# MiniMoto.net
KiCad netlist of a schematic drawn in EAGLE
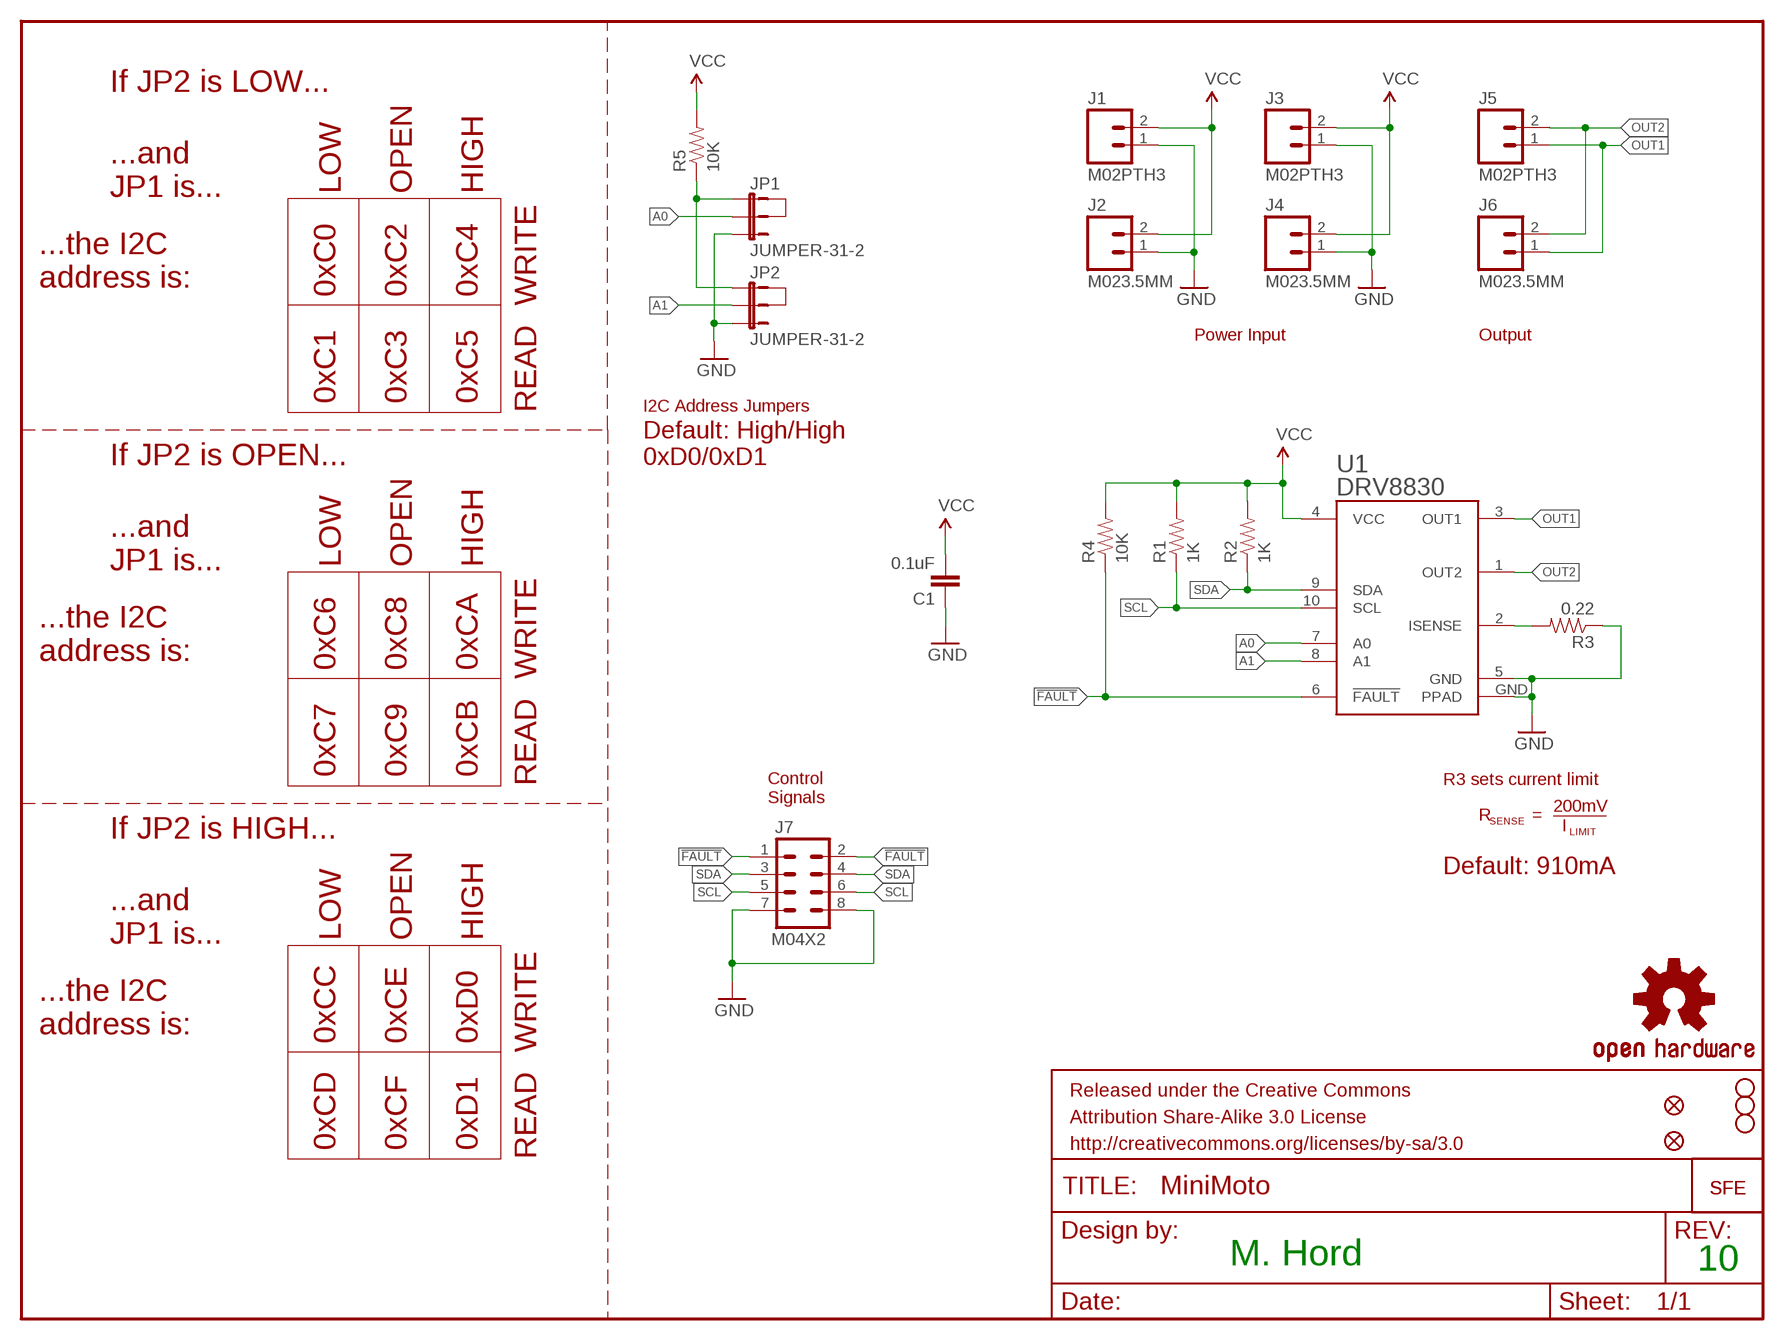
[diagram p0: schematic, sheet 1]

(export (version "E")
  (design (tool "Eeschema 10.0.6"))
  (components
    (comp (ref "C1")
      (value "0.1uF")
      (footprint "eagle-import:0603-CAP")
      (libsource (lib "eagle-import") (part "0.1UF-25V(+80/-20%)(0603)"))
    )
    (comp (ref "FID1")
      (value "FIDUCIALUFIDUCIAL")
      (footprint "eagle-import:MICRO-FIDUCIAL")
      (libsource (lib "eagle-import") (part "FIDUCIALUFIDUCIAL"))
    )
    (comp (ref "FID2")
      (value "FIDUCIALUFIDUCIAL")
      (footprint "eagle-import:MICRO-FIDUCIAL")
      (libsource (lib "eagle-import") (part "FIDUCIALUFIDUCIAL"))
    )
    (comp (ref "FRAME1")
      (value "FRAME-LETTER")
      (footprint "eagle-import:CREATIVE_COMMONS")
      (libsource (lib "eagle-import") (part "FRAME-LETTER"))
    )
    (comp (ref "J1")
      (value "M02PTH3")
      (footprint "eagle-import:1X02_LONGPADS")
      (libsource (lib "eagle-import") (part "M02PTH3"))
    )
    (comp (ref "J2")
      (value "M023.5MM")
      (footprint "eagle-import:SCREWTERMINAL-3.5MM-2")
      (libsource (lib "eagle-import") (part "M023.5MM"))
    )
    (comp (ref "J3")
      (value "M02PTH3")
      (footprint "eagle-import:1X02_LONGPADS")
      (libsource (lib "eagle-import") (part "M02PTH3"))
    )
    (comp (ref "J4")
      (value "M023.5MM")
      (footprint "eagle-import:SCREWTERMINAL-3.5MM-2")
      (libsource (lib "eagle-import") (part "M023.5MM"))
    )
    (comp (ref "J5")
      (value "M02PTH3")
      (footprint "eagle-import:1X02_LONGPADS")
      (libsource (lib "eagle-import") (part "M02PTH3"))
    )
    (comp (ref "J6")
      (value "M023.5MM")
      (footprint "eagle-import:SCREWTERMINAL-3.5MM-2")
      (libsource (lib "eagle-import") (part "M023.5MM"))
    )
    (comp (ref "J7")
      (value "M04X2")
      (footprint "eagle-import:2X4")
      (libsource (lib "eagle-import") (part "M04X2"))
    )
    (comp (ref "JP1")
      (value "JUMPER-31-2")
      (footprint "eagle-import:SJ_3_PASTE1&2")
      (libsource (lib "eagle-import") (part "JUMPER-31-2"))
    )
    (comp (ref "JP2")
      (value "JUMPER-31-2")
      (footprint "eagle-import:SJ_3_PASTE1&2")
      (libsource (lib "eagle-import") (part "JUMPER-31-2"))
    )
    (comp (ref "LOGO1")
      (value "LOGO-SFESK")
      (footprint "eagle-import:SFE-LOGO-FLAME")
      (libsource (lib "eagle-import") (part "LOGO-SFESK"))
    )
    (comp (ref "LOGO2")
      (value "OSHW-LOGOS")
      (footprint "eagle-import:OSHW-LOGO-S")
      (libsource (lib "eagle-import") (part "OSHW-LOGOS"))
    )
    (comp (ref "LOGO3")
      (value "LOGO-SFESK")
      (footprint "eagle-import:SFE-LOGO-FLAME")
      (libsource (lib "eagle-import") (part "LOGO-SFESK"))
    )
    (comp (ref "R1")
      (value "1K")
      (footprint "eagle-import:0603-RES")
      (libsource (lib "eagle-import") (part "1KOHM1/10W1%(0603)"))
    )
    (comp (ref "R2")
      (value "1K")
      (footprint "eagle-import:0603-RES")
      (libsource (lib "eagle-import") (part "1KOHM1/10W1%(0603)"))
    )
    (comp (ref "R3")
      (value "0.22")
      (footprint "eagle-import:0805")
      (libsource (lib "eagle-import") (part "0.22OHM1/4W1%(0805)"))
    )
    (comp (ref "R4")
      (value "10K")
      (footprint "eagle-import:0603-RES")
      (libsource (lib "eagle-import") (part "10KOHM1/10W1%(0603)0603"))
    )
    (comp (ref "R5")
      (value "10K")
      (footprint "eagle-import:0603-RES")
      (libsource (lib "eagle-import") (part "10KOHM1/10W1%(0603)0603"))
    )
    (comp (ref "STANDOFF1")
      (value "STAND-OFF")
      (footprint "eagle-import:STAND-OFF")
      (libsource (lib "eagle-import") (part "STAND-OFF"))
    )
    (comp (ref "STANDOFF2")
      (value "STAND-OFF")
      (footprint "eagle-import:STAND-OFF")
      (libsource (lib "eagle-import") (part "STAND-OFF"))
    )
    (comp (ref "STANDOFF3")
      (value "STAND-OFF")
      (footprint "eagle-import:STAND-OFF")
      (libsource (lib "eagle-import") (part "STAND-OFF"))
    )
    (comp (ref "U1")
      (value "DRV8830")
      (footprint "eagle-import:MSOP-10-GNDPAD")
      (libsource (lib "eagle-import") (part "DRV8830"))
    )
  )
  (nets
    (net (code "1") (name "/~{FAULT}") (class "Default")
      (node (ref "J7") (pin "1") (pinfunction "1_1") (pintype "passive"))
      (node (ref "J7") (pin "2") (pinfunction "2_2") (pintype "passive"))
      (node (ref "R4") (pin "1") (pinfunction "1_1") (pintype "passive"))
      (node (ref "U1") (pin "6") (pinfunction "~{FAULT}_6") (pintype "bidirectional"))
    )
    (net (code "2") (name "A0") (class "Default")
      (node (ref "JP1") (pin "2") (pinfunction "2_2") (pintype "passive"))
      (node (ref "U1") (pin "7") (pinfunction "A0_7") (pintype "bidirectional"))
    )
    (net (code "3") (name "A1") (class "Default")
      (node (ref "JP2") (pin "2") (pinfunction "2_2") (pintype "passive"))
      (node (ref "U1") (pin "8") (pinfunction "A1_8") (pintype "bidirectional"))
    )
    (net (code "4") (name "GND") (class "Default")
      (node (ref "C1") (pin "1") (pinfunction "1_1") (pintype "passive"))
      (node (ref "J1") (pin "1") (pinfunction "1_1") (pintype "passive"))
      (node (ref "J2") (pin "1") (pinfunction "1_1") (pintype "passive"))
      (node (ref "J3") (pin "1") (pinfunction "1_1") (pintype "passive"))
      (node (ref "J4") (pin "1") (pinfunction "1_1") (pintype "passive"))
      (node (ref "J7") (pin "7") (pinfunction "7_7") (pintype "passive"))
      (node (ref "J7") (pin "8") (pinfunction "8_8") (pintype "passive"))
      (node (ref "JP1") (pin "3") (pinfunction "3_3") (pintype "passive"))
      (node (ref "JP2") (pin "3") (pinfunction "3_3") (pintype "passive"))
      (node (ref "R3") (pin "1") (pinfunction "1_1") (pintype "passive"))
      (node (ref "U1") (pin "5") (pinfunction "GND_5") (pintype "bidirectional"))
      (node (ref "U1") (pin "GND") (pinfunction "PPAD_GND") (pintype "bidirectional"))
    )
    (net (code "5") (name "Net-(JP1-Pad1)") (class "Default")
      (node (ref "JP1") (pin "1") (pinfunction "1_1") (pintype "passive"))
      (node (ref "JP2") (pin "1") (pinfunction "1_1") (pintype "passive"))
      (node (ref "R5") (pin "1") (pinfunction "1_1") (pintype "passive"))
    )
    (net (code "6") (name "Net-(U1-ISENSE)") (class "Default")
      (node (ref "R3") (pin "2") (pinfunction "2_2") (pintype "passive"))
      (node (ref "U1") (pin "2") (pinfunction "ISENSE_2") (pintype "bidirectional"))
    )
    (net (code "7") (name "OUT1") (class "Default")
      (node (ref "J5") (pin "1") (pinfunction "1_1") (pintype "passive"))
      (node (ref "J6") (pin "1") (pinfunction "1_1") (pintype "passive"))
      (node (ref "U1") (pin "3") (pinfunction "OUT1_3") (pintype "bidirectional"))
    )
    (net (code "8") (name "OUT2") (class "Default")
      (node (ref "J5") (pin "2") (pinfunction "2_2") (pintype "passive"))
      (node (ref "J6") (pin "2") (pinfunction "2_2") (pintype "passive"))
      (node (ref "U1") (pin "1") (pinfunction "OUT2_1") (pintype "bidirectional"))
    )
    (net (code "9") (name "SCL") (class "Default")
      (node (ref "J7") (pin "5") (pinfunction "5_5") (pintype "passive"))
      (node (ref "J7") (pin "6") (pinfunction "6_6") (pintype "passive"))
      (node (ref "R1") (pin "1") (pinfunction "1_1") (pintype "passive"))
      (node (ref "U1") (pin "10") (pinfunction "SCL_10") (pintype "bidirectional"))
    )
    (net (code "10") (name "SDA") (class "Default")
      (node (ref "J7") (pin "3") (pinfunction "3_3") (pintype "passive"))
      (node (ref "J7") (pin "4") (pinfunction "4_4") (pintype "passive"))
      (node (ref "R2") (pin "1") (pinfunction "1_1") (pintype "passive"))
      (node (ref "U1") (pin "9") (pinfunction "SDA_9") (pintype "bidirectional"))
    )
    (net (code "11") (name "VCC") (class "Default")
      (node (ref "C1") (pin "2") (pinfunction "2_2") (pintype "passive"))
      (node (ref "J1") (pin "2") (pinfunction "2_2") (pintype "passive"))
      (node (ref "J2") (pin "2") (pinfunction "2_2") (pintype "passive"))
      (node (ref "J3") (pin "2") (pinfunction "2_2") (pintype "passive"))
      (node (ref "J4") (pin "2") (pinfunction "2_2") (pintype "passive"))
      (node (ref "R1") (pin "2") (pinfunction "2_2") (pintype "passive"))
      (node (ref "R2") (pin "2") (pinfunction "2_2") (pintype "passive"))
      (node (ref "R4") (pin "2") (pinfunction "2_2") (pintype "passive"))
      (node (ref "R5") (pin "2") (pinfunction "2_2") (pintype "passive"))
      (node (ref "U1") (pin "4") (pinfunction "VCC_4") (pintype "bidirectional"))
    )
  )
)
